# ICS40300-Silicon-Mic_Rev-A2.net
KiCad netlist of a schematic drawn in EAGLE
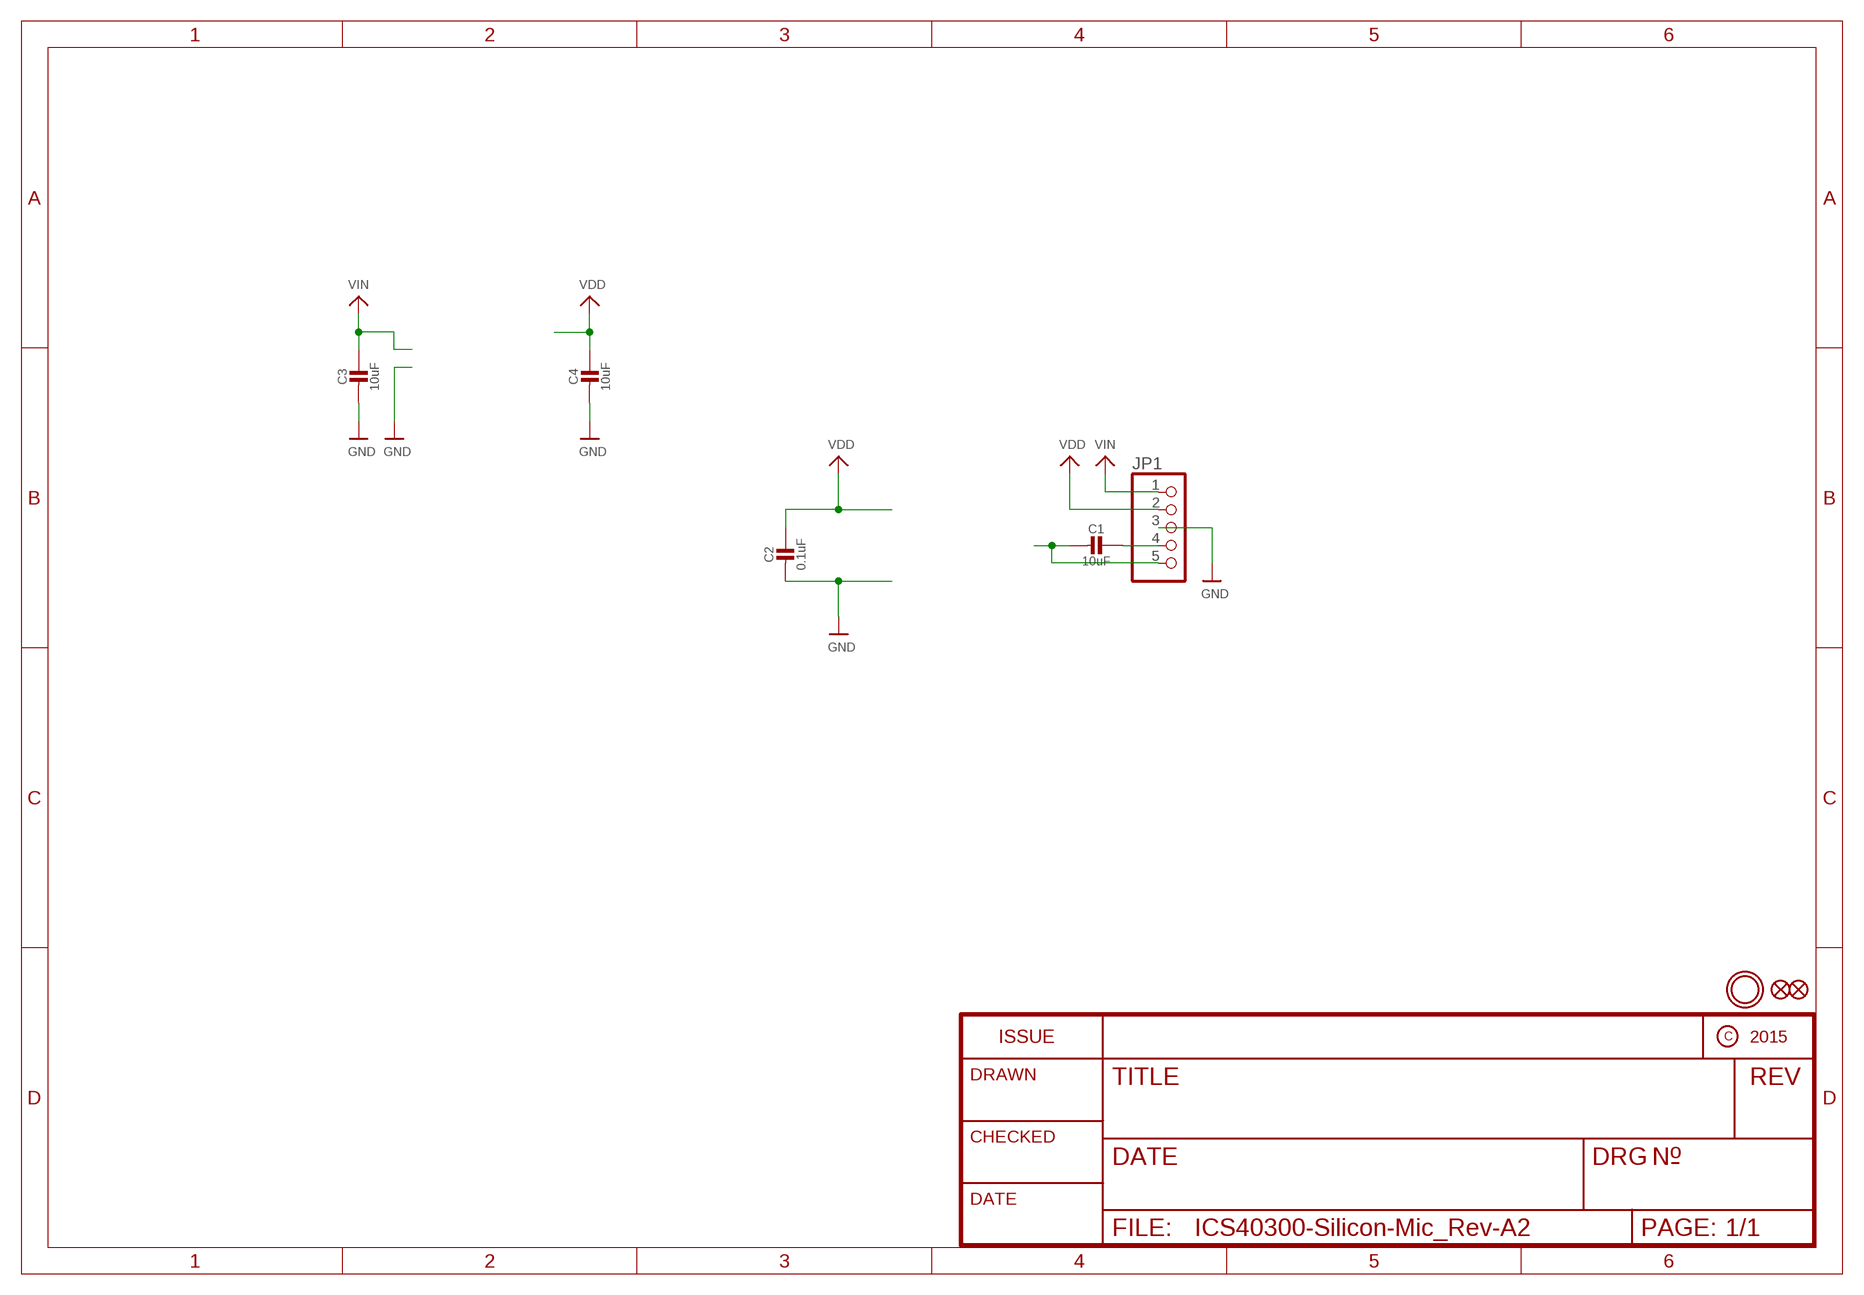
[diagram p0: schematic, sheet 1]

(export (version "E")
  (design (tool "Eeschema 10.0.6"))
  (components
    (comp (ref "C1")
      (value "10uF")
      (footprint "eagle-import:0805-NO")
      (libsource (lib "eagle-import") (part "CAP_CERAMIC0805-NOOUTLINE"))
    )
    (comp (ref "C2")
      (value "0.1uF")
      (footprint "eagle-import:0805-NO")
      (libsource (lib "eagle-import") (part "CAP_CERAMIC0805-NOOUTLINE"))
    )
    (comp (ref "C3")
      (value "10uF")
      (footprint "eagle-import:0805-NO")
      (libsource (lib "eagle-import") (part "CAP_CERAMIC0805-NOOUTLINE"))
    )
    (comp (ref "C4")
      (value "10uF")
      (footprint "eagle-import:0805-NO")
      (libsource (lib "eagle-import") (part "CAP_CERAMIC0805-NOOUTLINE"))
    )
    (comp (ref "FID1")
      (value "FIDUCIAL\"\"")
      (footprint "eagle-import:FIDUCIAL_1MM")
      (libsource (lib "eagle-import") (part "FIDUCIAL{dblquote}{dblquote}"))
    )
    (comp (ref "FID2")
      (value "FIDUCIAL\"\"")
      (footprint "eagle-import:FIDUCIAL_1MM")
      (libsource (lib "eagle-import") (part "FIDUCIAL{dblquote}{dblquote}"))
    )
    (comp (ref "JP1")
      (value "HEADER-1X576MIL")
      (footprint "eagle-import:1X05_ROUND_76")
      (libsource (lib "eagle-import") (part "HEADER-1X576MIL"))
    )
    (comp (ref "U$12")
      (value "MOUNTINGHOLE2.5")
      (footprint "eagle-import:MOUNTINGHOLE_2.5_PLATED")
      (libsource (lib "eagle-import") (part "MOUNTINGHOLE2.5"))
    )
  )
  (nets
    (net (code "1") (name "GND") (class "Default")
      (node (ref "C2") (pin "2") (pinfunction "2_2") (pintype "passive"))
      (node (ref "C3") (pin "2") (pinfunction "2_2") (pintype "passive"))
      (node (ref "C4") (pin "2") (pinfunction "2_2") (pintype "passive"))
      (node (ref "JP1") (pin "3") (pinfunction "3_3") (pintype "passive"))
    )
    (net (code "2") (name "Net-(C1-Pad1)") (class "Default")
      (node (ref "C1") (pin "1") (pinfunction "1_1") (pintype "passive"))
      (node (ref "JP1") (pin "4") (pinfunction "4_4") (pintype "passive"))
    )
    (net (code "3") (name "Net-(C1-Pad2)") (class "Default")
      (node (ref "C1") (pin "2") (pinfunction "2_2") (pintype "passive"))
      (node (ref "JP1") (pin "5") (pinfunction "5_5") (pintype "passive"))
    )
    (net (code "4") (name "VDD") (class "Default")
      (node (ref "C2") (pin "1") (pinfunction "1_1") (pintype "passive"))
      (node (ref "C4") (pin "1") (pinfunction "1_1") (pintype "passive"))
      (node (ref "JP1") (pin "2") (pinfunction "2_2") (pintype "passive"))
    )
    (net (code "5") (name "VIN") (class "Default")
      (node (ref "C3") (pin "1") (pinfunction "1_1") (pintype "passive"))
      (node (ref "JP1") (pin "1") (pinfunction "1_1") (pintype "passive"))
    )
  )
)
